# Power_Switch.net
KiCad netlist of a schematic drawn in Altium Designer
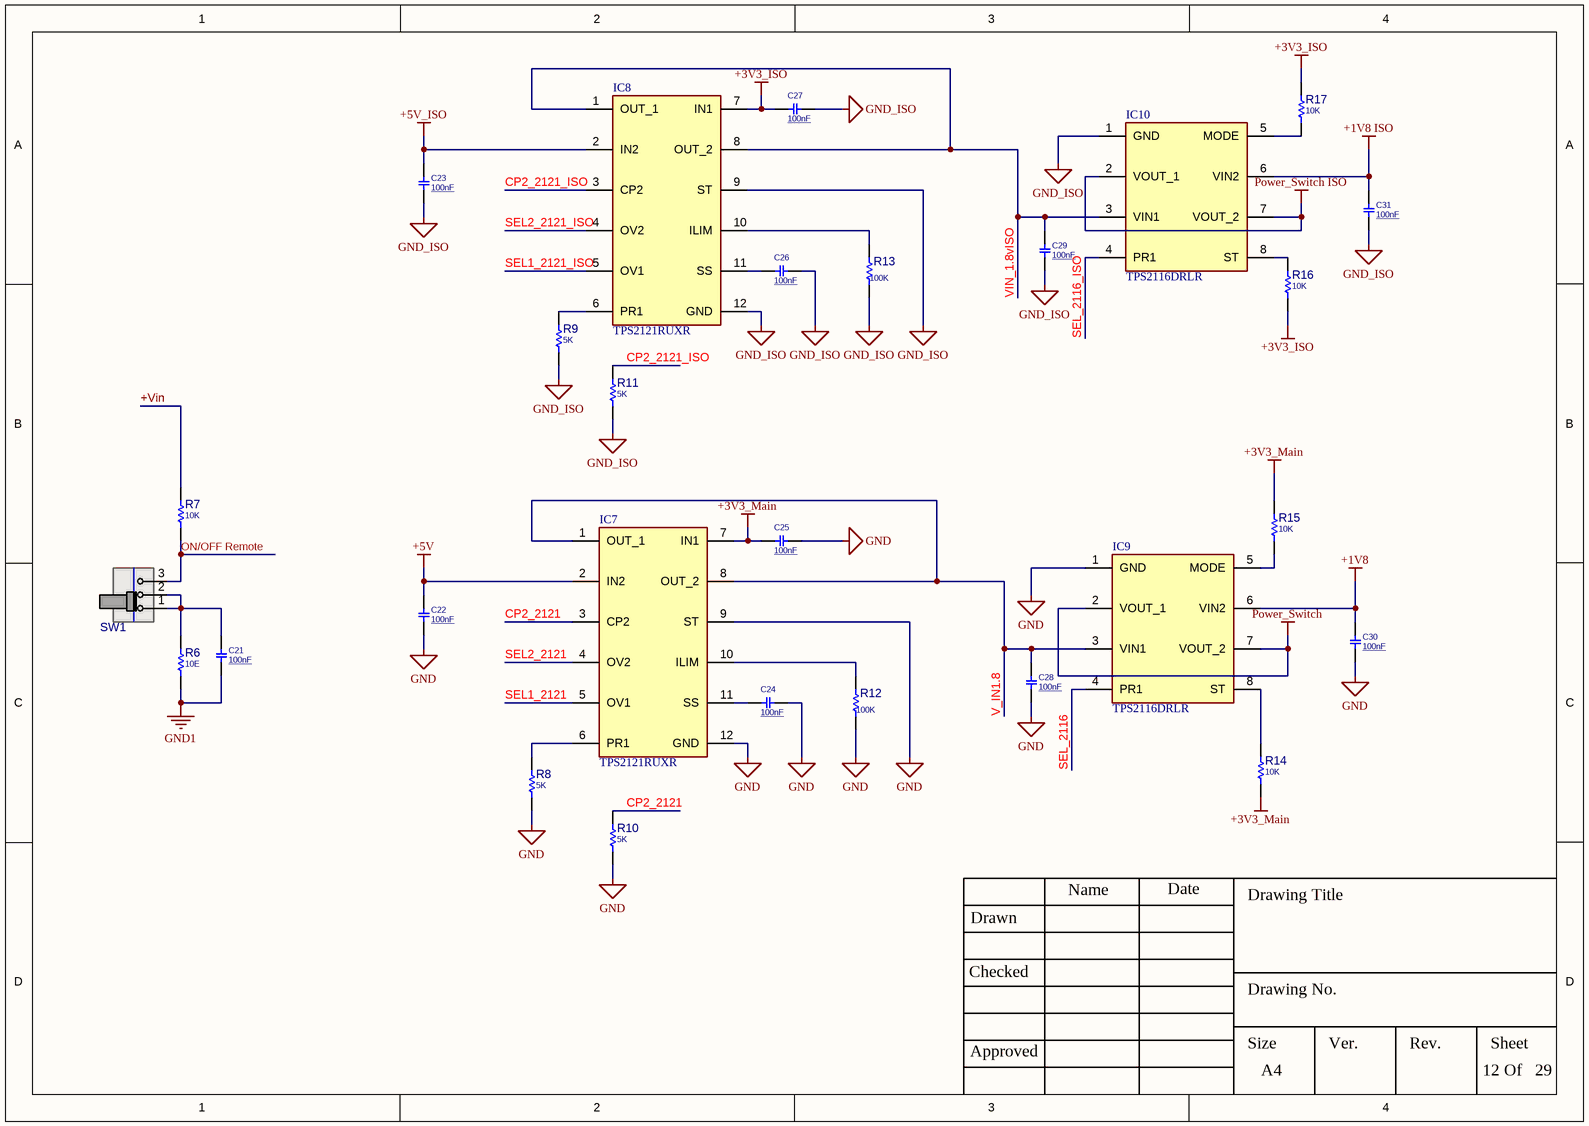
[diagram p0: Power Switch.SchDoc]

(export (version "E")
  (design (tool "Eeschema 10.0.6"))
  (components
    (comp (ref "C21")
      (value "100nF")
      (footprint "C1206")
      (description "CAP, MLCC, -F, -V, MATERIAL, -%, 0201")
      (fields (field (name "MANF_P#") "MANF_PART#"))
      (libsource (lib "passive_smd") (part "CAP_SMD_MLCC_1206"))
    )
    (comp (ref "C22")
      (value "100nF")
      (footprint "C0603")
      (description "CAP, MLCC, -F, -V, MATERIAL, -%, 0201")
      (fields (field (name "MANF_P#") "MANF_PART#"))
      (libsource (lib "passive_smd") (part "CAP_SMD_MLCC_0603"))
    )
    (comp (ref "C23")
      (value "100nF")
      (footprint "C0603")
      (description "CAP, MLCC, -F, -V, MATERIAL, -%, 0201")
      (fields (field (name "MANF_P#") "MANF_PART#"))
      (libsource (lib "passive_smd") (part "CAP_SMD_MLCC_0603"))
    )
    (comp (ref "C24")
      (value "100nF")
      (footprint "C0603")
      (description "CAP, MLCC, -F, -V, MATERIAL, -%, 0201")
      (fields (field (name "MANF_P#") "MANF_PART#"))
      (libsource (lib "passive_smd") (part "CAP_SMD_MLCC_0603"))
    )
    (comp (ref "C25")
      (value "100nF")
      (footprint "C0603")
      (description "CAP, MLCC, -F, -V, MATERIAL, -%, 0201")
      (fields (field (name "MANF_P#") "MANF_PART#"))
      (libsource (lib "passive_smd") (part "CAP_SMD_MLCC_0603"))
    )
    (comp (ref "C26")
      (value "100nF")
      (footprint "C0603")
      (description "CAP, MLCC, -F, -V, MATERIAL, -%, 0201")
      (fields (field (name "MANF_P#") "MANF_PART#"))
      (libsource (lib "passive_smd") (part "CAP_SMD_MLCC_0603"))
    )
    (comp (ref "C27")
      (value "100nF")
      (footprint "C0603")
      (description "CAP, MLCC, -F, -V, MATERIAL, -%, 0201")
      (fields (field (name "MANF_P#") "MANF_PART#"))
      (libsource (lib "passive_smd") (part "CAP_SMD_MLCC_0603"))
    )
    (comp (ref "C28")
      (value "100nF")
      (footprint "C0603")
      (description "CAP, MLCC, -F, -V, MATERIAL, -%, 0201")
      (fields (field (name "MANF_P#") "MANF_PART#"))
      (libsource (lib "passive_smd") (part "CAP_SMD_MLCC_0603"))
    )
    (comp (ref "C29")
      (value "100nF")
      (footprint "C0603")
      (description "CAP, MLCC, -F, -V, MATERIAL, -%, 0201")
      (fields (field (name "MANF_P#") "MANF_PART#"))
      (libsource (lib "passive_smd") (part "CAP_SMD_MLCC_0603"))
    )
    (comp (ref "C30")
      (value "100nF")
      (footprint "C0603")
      (description "CAP, MLCC, -F, -V, MATERIAL, -%, 0201")
      (fields (field (name "MANF_P#") "MANF_PART#"))
      (libsource (lib "passive_smd") (part "CAP_SMD_MLCC_0603"))
    )
    (comp (ref "C31")
      (value "100nF")
      (footprint "C0603")
      (description "CAP, MLCC, -F, -V, MATERIAL, -%, 0201")
      (fields (field (name "MANF_P#") "MANF_PART#"))
      (libsource (lib "passive_smd") (part "CAP_SMD_MLCC_0603"))
    )
    (comp (ref "IC7")
      (value "TPS2121RUXR")
      (footprint "SamacSys:TPS2121RUXR")
      (description "Integrated Circuit")
      (fields (field (name "MOUSER PART NUMBER") "595-TPS2121RUXR"))
      (libsource (lib "SamacSys") (part "TPS2121RUXR"))
    )
    (comp (ref "IC8")
      (value "TPS2121RUXR")
      (footprint "SamacSys:TPS2121RUXR")
      (description "Integrated Circuit")
      (fields (field (name "MOUSER PART NUMBER") "595-TPS2121RUXR"))
      (libsource (lib "SamacSys") (part "TPS2121RUXR"))
    )
    (comp (ref "IC9")
      (value "TPS2116DRLR")
      (footprint "SamacSys:SOTFL50P160X60-8N")
      (description "Integrated Circuit")
      (fields (field (name "MOUSER PART NUMBER") "595-TPS2116DRLR"))
      (libsource (lib "SamacSys") (part "TPS2116DRLR"))
    )
    (comp (ref "IC10")
      (value "TPS2116DRLR")
      (footprint "SamacSys:SOTFL50P160X60-8N")
      (description "Integrated Circuit")
      (fields (field (name "MOUSER PART NUMBER") "595-TPS2116DRLR"))
      (libsource (lib "SamacSys") (part "TPS2116DRLR"))
    )
    (comp (ref "R6")
      (value "10E")
      (footprint "R0603")
      (description "RESISTOR, SMD")
      (libsource (lib "passive_smd") (part "RES_SMD_0603"))
    )
    (comp (ref "R7")
      (value "10K")
      (footprint "R1206")
      (description "RESISTOR, SMD")
      (libsource (lib "passive_smd") (part "RES_SMD_1206"))
    )
    (comp (ref "R8")
      (value "5K")
      (footprint "R0603")
      (description "RESISTOR, SMD")
      (libsource (lib "passive_smd") (part "RES_SMD_0603"))
    )
    (comp (ref "R9")
      (value "5K")
      (footprint "R0603")
      (description "RESISTOR, SMD")
      (libsource (lib "passive_smd") (part "RES_SMD_0603"))
    )
    (comp (ref "R10")
      (value "5K")
      (footprint "R0603")
      (description "RESISTOR, SMD")
      (libsource (lib "passive_smd") (part "RES_SMD_0603"))
    )
    (comp (ref "R11")
      (value "5K")
      (footprint "R0603")
      (description "RESISTOR, SMD")
      (libsource (lib "passive_smd") (part "RES_SMD_0603"))
    )
    (comp (ref "R12")
      (value "100K")
      (footprint "R0603")
      (description "RESISTOR, SMD")
      (fields (field (name "Comment") "0R"))
      (libsource (lib "passive_smd") (part "RES_SMD_0603"))
    )
    (comp (ref "R13")
      (value "100K")
      (footprint "R0603")
      (description "RESISTOR, SMD")
      (fields (field (name "Comment") "10K"))
      (libsource (lib "passive_smd") (part "RES_SMD_0603"))
    )
    (comp (ref "R14")
      (value "10K")
      (footprint "R0603")
      (description "RESISTOR, SMD")
      (libsource (lib "passive_smd") (part "RES_SMD_0603"))
    )
    (comp (ref "R15")
      (value "10K")
      (footprint "R0603")
      (description "RESISTOR, SMD")
      (libsource (lib "passive_smd") (part "RES_SMD_0603"))
    )
    (comp (ref "R16")
      (value "10K")
      (footprint "R0603")
      (description "RESISTOR, SMD")
      (libsource (lib "passive_smd") (part "RES_SMD_0603"))
    )
    (comp (ref "R17")
      (value "10K")
      (footprint "R0603")
      (description "RESISTOR, SMD")
      (libsource (lib "passive_smd") (part "RES_SMD_0603"))
    )
    (comp (ref "SW1")
      (value "SlideSwitch")
      (footprint "SWSLIDT_SPDT_R_8X4")
      (description "SWITCH, SLIDE, SPDT, 8X4mm, THD")
      (fields (field (name "MANF") "Apem") (field (name "MANF_PART#") "MHSS1105"))
      (libsource (lib "switch_slide") (part "SWSLIDT_SPDT_R_8X4"))
    )
  )
  (nets
    (net (code "1") (name "+1V8") (class "Default")
      (node (ref "C30") (pin "1") (pinfunction "1_1") (pintype "passive"))
      (node (ref "IC9") (pin "6") (pinfunction "VIN2_6") (pintype "passive"))
    )
    (net (code "2") (name "+1V8 ISO") (class "Default")
      (node (ref "C31") (pin "1") (pinfunction "1_1") (pintype "passive"))
      (node (ref "IC10") (pin "6") (pinfunction "VIN2_6") (pintype "passive"))
    )
    (net (code "3") (name "+3V3_ISO") (class "Default")
      (node (ref "C27") (pin "1") (pinfunction "1_1") (pintype "passive"))
      (node (ref "IC8") (pin "7") (pinfunction "IN1_7") (pintype "passive"))
      (node (ref "R16") (pin "2") (pinfunction "2_2") (pintype "passive"))
      (node (ref "R17") (pin "2") (pinfunction "2_2") (pintype "passive"))
    )
    (net (code "4") (name "+3V3_Main") (class "Default")
      (node (ref "C25") (pin "1") (pinfunction "1_1") (pintype "passive"))
      (node (ref "IC7") (pin "7") (pinfunction "IN1_7") (pintype "passive"))
      (node (ref "R14") (pin "2") (pinfunction "2_2") (pintype "passive"))
      (node (ref "R15") (pin "2") (pinfunction "2_2") (pintype "passive"))
    )
    (net (code "5") (name "+5V") (class "Default")
      (node (ref "C22") (pin "1") (pinfunction "1_1") (pintype "passive"))
      (node (ref "IC7") (pin "2") (pinfunction "IN2_2") (pintype "passive"))
    )
    (net (code "6") (name "+5V_ISO") (class "Default")
      (node (ref "C23") (pin "1") (pinfunction "1_1") (pintype "passive"))
      (node (ref "IC8") (pin "2") (pinfunction "IN2_2") (pintype "passive"))
    )
    (net (code "7") (name "/+Vin") (class "Default")
      (node (ref "R7") (pin "1") (pinfunction "1_1") (pintype "passive"))
    )
    (net (code "8") (name "/CP2_2121") (class "Default")
      (node (ref "IC7") (pin "3") (pinfunction "CP2_3") (pintype "passive"))
      (node (ref "R10") (pin "2") (pinfunction "2_2") (pintype "passive"))
    )
    (net (code "9") (name "/CP2_2121_ISO") (class "Default")
      (node (ref "IC8") (pin "3") (pinfunction "CP2_3") (pintype "passive"))
      (node (ref "R11") (pin "2") (pinfunction "2_2") (pintype "passive"))
    )
    (net (code "10") (name "/ON{slash}OFF Remote") (class "Default")
      (node (ref "R7") (pin "2") (pinfunction "2_2") (pintype "passive"))
      (node (ref "SW1") (pin "3") (pinfunction "P4_3") (pintype "passive"))
    )
    (net (code "11") (name "/SEL1_2121") (class "Default")
      (node (ref "IC7") (pin "5") (pinfunction "OV1_5") (pintype "passive"))
    )
    (net (code "12") (name "/SEL1_2121_ISO") (class "Default")
      (node (ref "IC8") (pin "5") (pinfunction "OV1_5") (pintype "passive"))
    )
    (net (code "13") (name "/SEL2_2121") (class "Default")
      (node (ref "IC7") (pin "4") (pinfunction "OV2_4") (pintype "passive"))
    )
    (net (code "14") (name "/SEL2_2121_ISO") (class "Default")
      (node (ref "IC8") (pin "4") (pinfunction "OV2_4") (pintype "passive"))
    )
    (net (code "15") (name "/SEL_2116") (class "Default")
      (node (ref "IC9") (pin "4") (pinfunction "PR1_4") (pintype "passive"))
    )
    (net (code "16") (name "/SEL_2116_ISO") (class "Default")
      (node (ref "IC10") (pin "4") (pinfunction "PR1_4") (pintype "passive"))
    )
    (net (code "17") (name "/VIN_1.8vISO") (class "Default")
      (node (ref "C29") (pin "1") (pinfunction "1_1") (pintype "passive"))
      (node (ref "IC10") (pin "3") (pinfunction "VIN1_3") (pintype "passive"))
      (node (ref "IC8") (pin "1") (pinfunction "OUT_1_1") (pintype "passive"))
      (node (ref "IC8") (pin "8") (pinfunction "OUT_2_8") (pintype "passive"))
    )
    (net (code "18") (name "/V_IN1.8") (class "Default")
      (node (ref "C28") (pin "1") (pinfunction "1_1") (pintype "passive"))
      (node (ref "IC7") (pin "1") (pinfunction "OUT_1_1") (pintype "passive"))
      (node (ref "IC7") (pin "8") (pinfunction "OUT_2_8") (pintype "passive"))
      (node (ref "IC9") (pin "3") (pinfunction "VIN1_3") (pintype "passive"))
    )
    (net (code "19") (name "GND") (class "Default")
      (node (ref "C22") (pin "2") (pinfunction "2_2") (pintype "passive"))
      (node (ref "C24") (pin "1") (pinfunction "1_1") (pintype "passive"))
      (node (ref "C25") (pin "2") (pinfunction "2_2") (pintype "passive"))
      (node (ref "C28") (pin "2") (pinfunction "2_2") (pintype "passive"))
      (node (ref "C30") (pin "2") (pinfunction "2_2") (pintype "passive"))
      (node (ref "IC7") (pin "12") (pinfunction "GND_12") (pintype "passive"))
      (node (ref "IC7") (pin "9") (pinfunction "ST_9") (pintype "passive"))
      (node (ref "IC9") (pin "1") (pinfunction "GND_1") (pintype "passive"))
      (node (ref "R10") (pin "1") (pinfunction "1_1") (pintype "passive"))
      (node (ref "R12") (pin "1") (pinfunction "1_1") (pintype "passive"))
      (node (ref "R8") (pin "1") (pinfunction "1_1") (pintype "passive"))
    )
    (net (code "20") (name "GND1") (class "Default")
      (node (ref "C21") (pin "1") (pinfunction "1_1") (pintype "passive"))
      (node (ref "R6") (pin "1") (pinfunction "1_1") (pintype "passive"))
    )
    (net (code "21") (name "GND_ISO") (class "Default")
      (node (ref "C23") (pin "2") (pinfunction "2_2") (pintype "passive"))
      (node (ref "C26") (pin "1") (pinfunction "1_1") (pintype "passive"))
      (node (ref "C27") (pin "2") (pinfunction "2_2") (pintype "passive"))
      (node (ref "C29") (pin "2") (pinfunction "2_2") (pintype "passive"))
      (node (ref "C31") (pin "2") (pinfunction "2_2") (pintype "passive"))
      (node (ref "IC10") (pin "1") (pinfunction "GND_1") (pintype "passive"))
      (node (ref "IC8") (pin "12") (pinfunction "GND_12") (pintype "passive"))
      (node (ref "IC8") (pin "9") (pinfunction "ST_9") (pintype "passive"))
      (node (ref "R11") (pin "1") (pinfunction "1_1") (pintype "passive"))
      (node (ref "R13") (pin "1") (pinfunction "1_1") (pintype "passive"))
      (node (ref "R9") (pin "1") (pinfunction "1_1") (pintype "passive"))
    )
    (net (code "22") (name "Net-(IC7-ILIM)") (class "Default")
      (node (ref "IC7") (pin "10") (pinfunction "ILIM_10") (pintype "passive"))
      (node (ref "R12") (pin "2") (pinfunction "2_2") (pintype "passive"))
    )
    (net (code "23") (name "Net-(IC7-PR1)") (class "Default")
      (node (ref "IC7") (pin "6") (pinfunction "PR1_6") (pintype "passive"))
      (node (ref "R8") (pin "2") (pinfunction "2_2") (pintype "passive"))
    )
    (net (code "24") (name "Net-(IC7-SS)") (class "Default")
      (node (ref "C24") (pin "2") (pinfunction "2_2") (pintype "passive"))
      (node (ref "IC7") (pin "11") (pinfunction "SS_11") (pintype "passive"))
    )
    (net (code "25") (name "Net-(IC8-ILIM)") (class "Default")
      (node (ref "IC8") (pin "10") (pinfunction "ILIM_10") (pintype "passive"))
      (node (ref "R13") (pin "2") (pinfunction "2_2") (pintype "passive"))
    )
    (net (code "26") (name "Net-(IC8-PR1)") (class "Default")
      (node (ref "IC8") (pin "6") (pinfunction "PR1_6") (pintype "passive"))
      (node (ref "R9") (pin "2") (pinfunction "2_2") (pintype "passive"))
    )
    (net (code "27") (name "Net-(IC8-SS)") (class "Default")
      (node (ref "C26") (pin "2") (pinfunction "2_2") (pintype "passive"))
      (node (ref "IC8") (pin "11") (pinfunction "SS_11") (pintype "passive"))
    )
    (net (code "28") (name "Net-(IC9-MODE)") (class "Default")
      (node (ref "IC9") (pin "5") (pinfunction "MODE_5") (pintype "passive"))
      (node (ref "R15") (pin "1") (pinfunction "1_1") (pintype "passive"))
    )
    (net (code "29") (name "Net-(IC9-ST)") (class "Default")
      (node (ref "IC9") (pin "8") (pinfunction "ST_8") (pintype "passive"))
      (node (ref "R14") (pin "1") (pinfunction "1_1") (pintype "passive"))
    )
    (net (code "30") (name "Net-(IC10-MODE)") (class "Default")
      (node (ref "IC10") (pin "5") (pinfunction "MODE_5") (pintype "passive"))
      (node (ref "R17") (pin "1") (pinfunction "1_1") (pintype "passive"))
    )
    (net (code "31") (name "Net-(IC10-ST)") (class "Default")
      (node (ref "IC10") (pin "8") (pinfunction "ST_8") (pintype "passive"))
      (node (ref "R16") (pin "1") (pinfunction "1_1") (pintype "passive"))
    )
    (net (code "32") (name "Net-(SW1-P1)") (class "Default")
      (node (ref "C21") (pin "2") (pinfunction "2_2") (pintype "passive"))
      (node (ref "R6") (pin "2") (pinfunction "2_2") (pintype "passive"))
      (node (ref "SW1") (pin "1") (pinfunction "P1_1") (pintype "passive"))
      (node (ref "SW1") (pin "2") (pinfunction "P3_2") (pintype "passive"))
    )
    (net (code "33") (name "Power_Switch") (class "Default")
      (node (ref "IC9") (pin "2") (pinfunction "VOUT_1_2") (pintype "passive"))
      (node (ref "IC9") (pin "7") (pinfunction "VOUT_2_7") (pintype "passive"))
    )
    (net (code "34") (name "Power_Switch ISO") (class "Default")
      (node (ref "IC10") (pin "2") (pinfunction "VOUT_1_2") (pintype "passive"))
      (node (ref "IC10") (pin "7") (pinfunction "VOUT_2_7") (pintype "passive"))
    )
  )
)
